# WAM-D.net
KiCad netlist of a schematic drawn in EAGLE
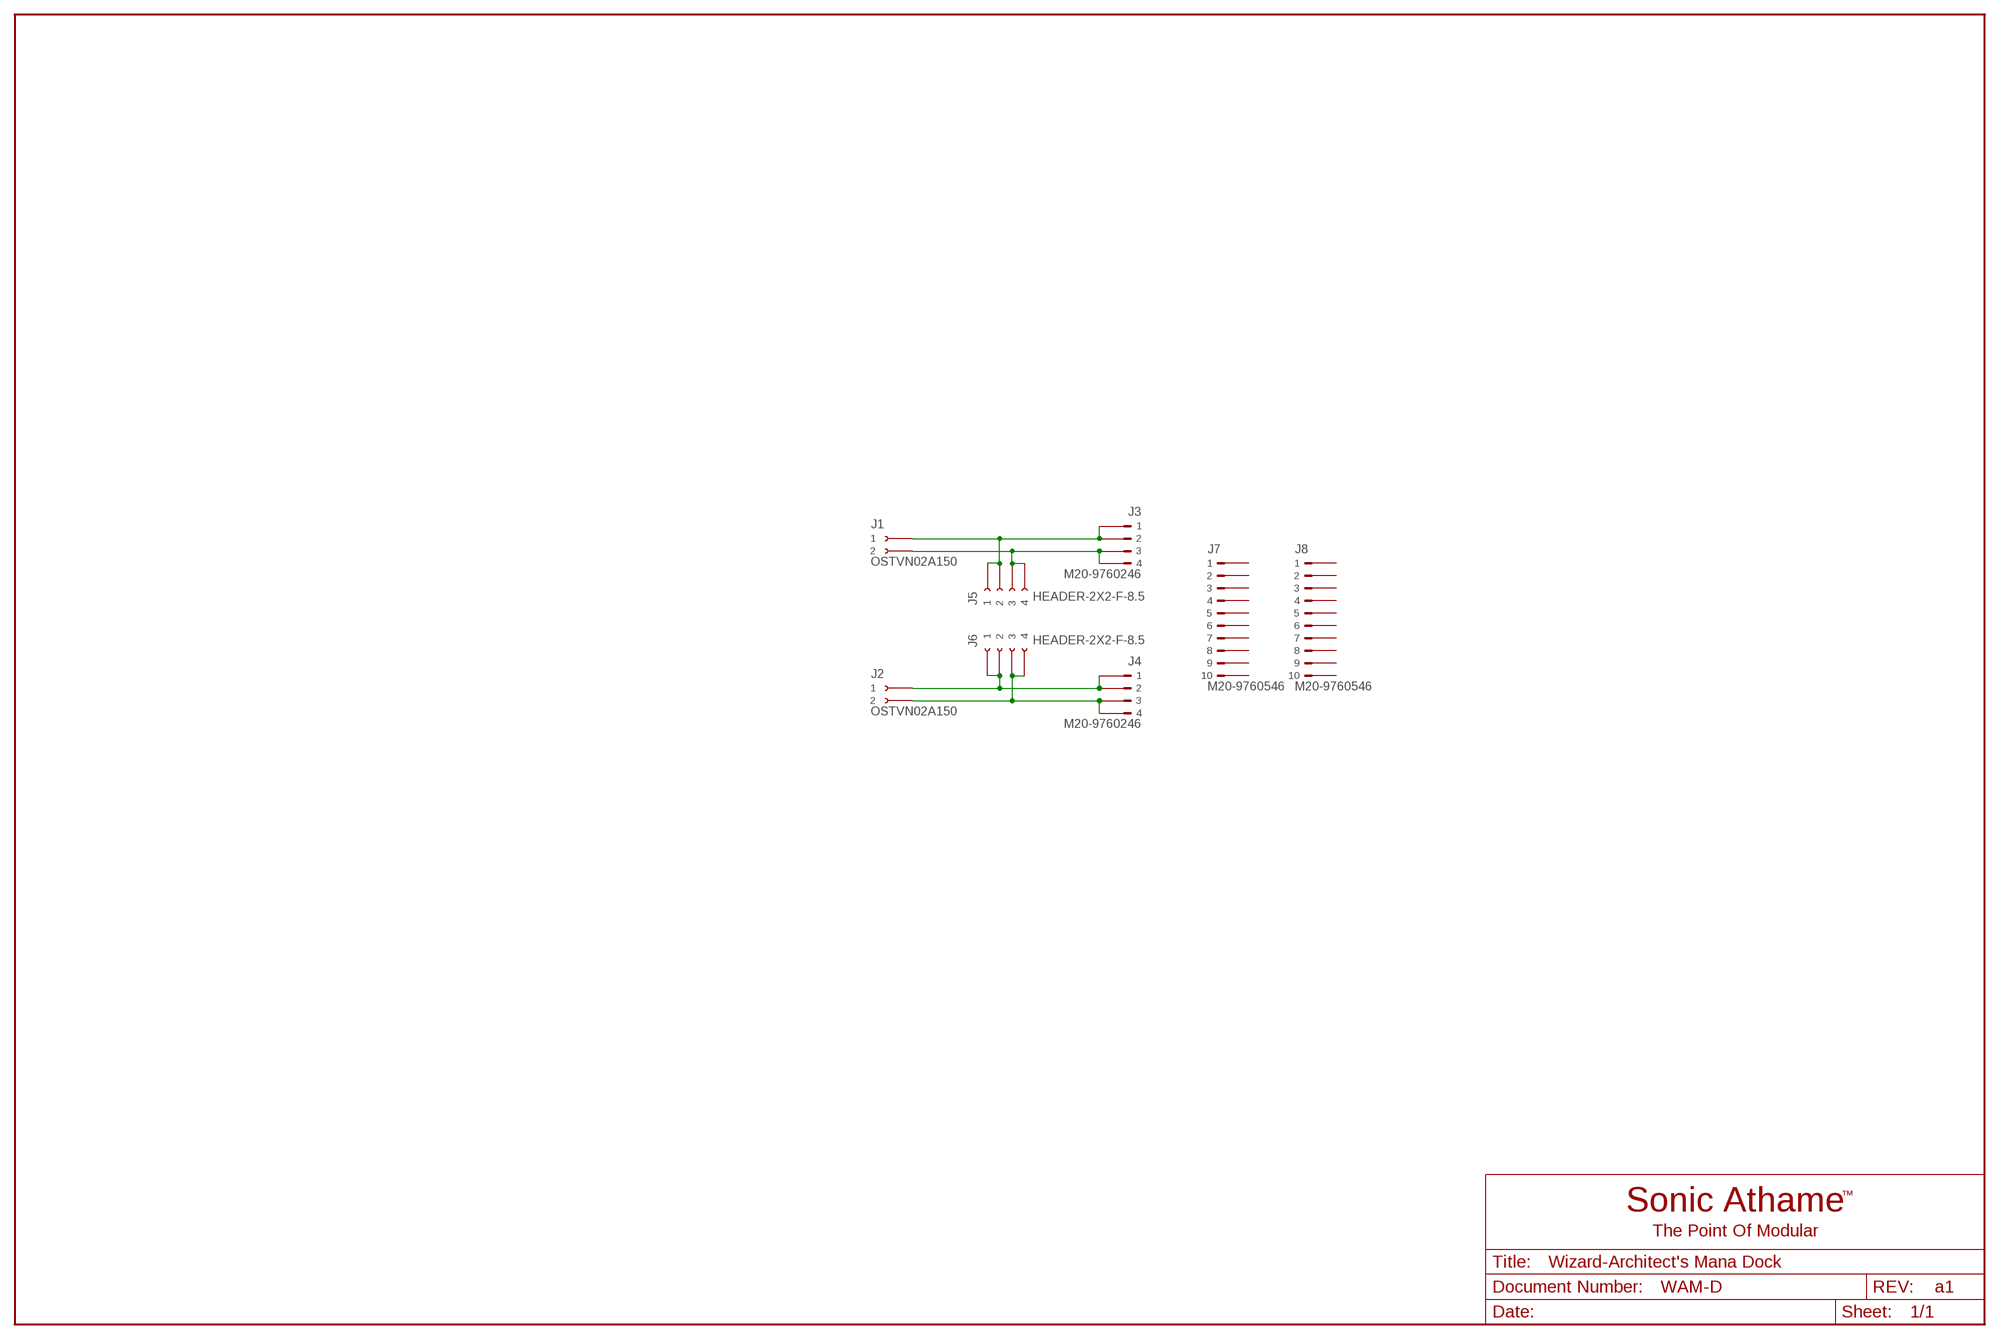
[diagram p0: schematic, sheet 1]

(export (version "E")
  (design (tool "Eeschema 10.0.6"))
  (components
    (comp (ref "J1")
      (value "OSTVN02A150")
      (footprint "eagle-import:OSTVN02A150")
      (libsource (lib "eagle-import") (part "OSTVN02A150"))
    )
    (comp (ref "J2")
      (value "OSTVN02A150")
      (footprint "eagle-import:OSTVN02A150")
      (libsource (lib "eagle-import") (part "OSTVN02A150"))
    )
    (comp (ref "J3")
      (value "M20-9760246")
      (footprint "eagle-import:HDRV4W64P254_2X2_508X508X834B")
      (libsource (lib "eagle-import") (part "M20-9760246"))
    )
    (comp (ref "J4")
      (value "M20-9760246")
      (footprint "eagle-import:HDRV4W64P254_2X2_508X508X834B")
      (libsource (lib "eagle-import") (part "M20-9760246"))
    )
    (comp (ref "J5")
      (value "HEADER-2X2-F-8.5")
      (footprint "eagle-import:HDRVR4W75P254_2X2_558X508X850B")
      (libsource (lib "eagle-import") (part "HEADER-2X2-F-8.5"))
    )
    (comp (ref "J6")
      (value "HEADER-2X2-F-8.5")
      (footprint "eagle-import:HDRVR4W75P254_2X2_558X508X850B")
      (libsource (lib "eagle-import") (part "HEADER-2X2-F-8.5"))
    )
    (comp (ref "J7")
      (value "M20-9760546")
      (footprint "eagle-import:HDRV10W64P254_2X5_1270X508X834B")
      (libsource (lib "eagle-import") (part "M20-9760546"))
    )
    (comp (ref "J8")
      (value "M20-9760546")
      (footprint "eagle-import:HDRV10W64P254_2X5_1270X508X834B")
      (libsource (lib "eagle-import") (part "M20-9760546"))
    )
  )
  (nets
    (net (code "1") (name "Net-(J1-1)") (class "Default")
      (node (ref "J1") (pin "P$1") (pinfunction "1_P$1") (pintype "passive"))
      (node (ref "J3") (pin "1") (pinfunction "1_1") (pintype "passive"))
      (node (ref "J3") (pin "2") (pinfunction "2_2") (pintype "passive"))
      (node (ref "J5") (pin "1") (pinfunction "1_1") (pintype "passive"))
      (node (ref "J5") (pin "2") (pinfunction "2_2") (pintype "passive"))
    )
    (net (code "2") (name "Net-(J1-2)") (class "Default")
      (node (ref "J1") (pin "P$2") (pinfunction "2_P$2") (pintype "passive"))
      (node (ref "J3") (pin "3") (pinfunction "3_3") (pintype "passive"))
      (node (ref "J3") (pin "4") (pinfunction "4_4") (pintype "passive"))
      (node (ref "J5") (pin "3") (pinfunction "3_3") (pintype "passive"))
      (node (ref "J5") (pin "4") (pinfunction "4_4") (pintype "passive"))
    )
    (net (code "3") (name "Net-(J2-1)") (class "Default")
      (node (ref "J2") (pin "P$1") (pinfunction "1_P$1") (pintype "passive"))
      (node (ref "J4") (pin "1") (pinfunction "1_1") (pintype "passive"))
      (node (ref "J4") (pin "2") (pinfunction "2_2") (pintype "passive"))
      (node (ref "J6") (pin "1") (pinfunction "1_1") (pintype "passive"))
      (node (ref "J6") (pin "2") (pinfunction "2_2") (pintype "passive"))
    )
    (net (code "4") (name "Net-(J2-2)") (class "Default")
      (node (ref "J2") (pin "P$2") (pinfunction "2_P$2") (pintype "passive"))
      (node (ref "J4") (pin "3") (pinfunction "3_3") (pintype "passive"))
      (node (ref "J4") (pin "4") (pinfunction "4_4") (pintype "passive"))
      (node (ref "J6") (pin "3") (pinfunction "3_3") (pintype "passive"))
      (node (ref "J6") (pin "4") (pinfunction "4_4") (pintype "passive"))
    )
    (net (code "5") (name "unconnected-(J7-Pad1)") (class "Default")
      (node (ref "J7") (pin "1") (pinfunction "1_1") (pintype "passive"))
    )
    (net (code "6") (name "unconnected-(J7-Pad2)") (class "Default")
      (node (ref "J7") (pin "2") (pinfunction "2_2") (pintype "passive"))
    )
    (net (code "7") (name "unconnected-(J7-Pad3)") (class "Default")
      (node (ref "J7") (pin "3") (pinfunction "3_3") (pintype "passive"))
    )
    (net (code "8") (name "unconnected-(J7-Pad4)") (class "Default")
      (node (ref "J7") (pin "4") (pinfunction "4_4") (pintype "passive"))
    )
    (net (code "9") (name "unconnected-(J7-Pad5)") (class "Default")
      (node (ref "J7") (pin "5") (pinfunction "5_5") (pintype "passive"))
    )
    (net (code "10") (name "unconnected-(J7-Pad6)") (class "Default")
      (node (ref "J7") (pin "6") (pinfunction "6_6") (pintype "passive"))
    )
    (net (code "11") (name "unconnected-(J7-Pad7)") (class "Default")
      (node (ref "J7") (pin "7") (pinfunction "7_7") (pintype "passive"))
    )
    (net (code "12") (name "unconnected-(J7-Pad8)") (class "Default")
      (node (ref "J7") (pin "8") (pinfunction "8_8") (pintype "passive"))
    )
    (net (code "13") (name "unconnected-(J7-Pad9)") (class "Default")
      (node (ref "J7") (pin "9") (pinfunction "9_9") (pintype "passive"))
    )
    (net (code "14") (name "unconnected-(J7-Pad10)") (class "Default")
      (node (ref "J7") (pin "10") (pinfunction "10_10") (pintype "passive"))
    )
    (net (code "15") (name "unconnected-(J8-Pad1)") (class "Default")
      (node (ref "J8") (pin "1") (pinfunction "1_1") (pintype "passive"))
    )
    (net (code "16") (name "unconnected-(J8-Pad2)") (class "Default")
      (node (ref "J8") (pin "2") (pinfunction "2_2") (pintype "passive"))
    )
    (net (code "17") (name "unconnected-(J8-Pad3)") (class "Default")
      (node (ref "J8") (pin "3") (pinfunction "3_3") (pintype "passive"))
    )
    (net (code "18") (name "unconnected-(J8-Pad4)") (class "Default")
      (node (ref "J8") (pin "4") (pinfunction "4_4") (pintype "passive"))
    )
    (net (code "19") (name "unconnected-(J8-Pad5)") (class "Default")
      (node (ref "J8") (pin "5") (pinfunction "5_5") (pintype "passive"))
    )
    (net (code "20") (name "unconnected-(J8-Pad6)") (class "Default")
      (node (ref "J8") (pin "6") (pinfunction "6_6") (pintype "passive"))
    )
    (net (code "21") (name "unconnected-(J8-Pad7)") (class "Default")
      (node (ref "J8") (pin "7") (pinfunction "7_7") (pintype "passive"))
    )
    (net (code "22") (name "unconnected-(J8-Pad8)") (class "Default")
      (node (ref "J8") (pin "8") (pinfunction "8_8") (pintype "passive"))
    )
    (net (code "23") (name "unconnected-(J8-Pad9)") (class "Default")
      (node (ref "J8") (pin "9") (pinfunction "9_9") (pintype "passive"))
    )
    (net (code "24") (name "unconnected-(J8-Pad10)") (class "Default")
      (node (ref "J8") (pin "10") (pinfunction "10_10") (pintype "passive"))
    )
  )
)
